# DAC_Production.net
KiCad netlist of a schematic drawn in EAGLE
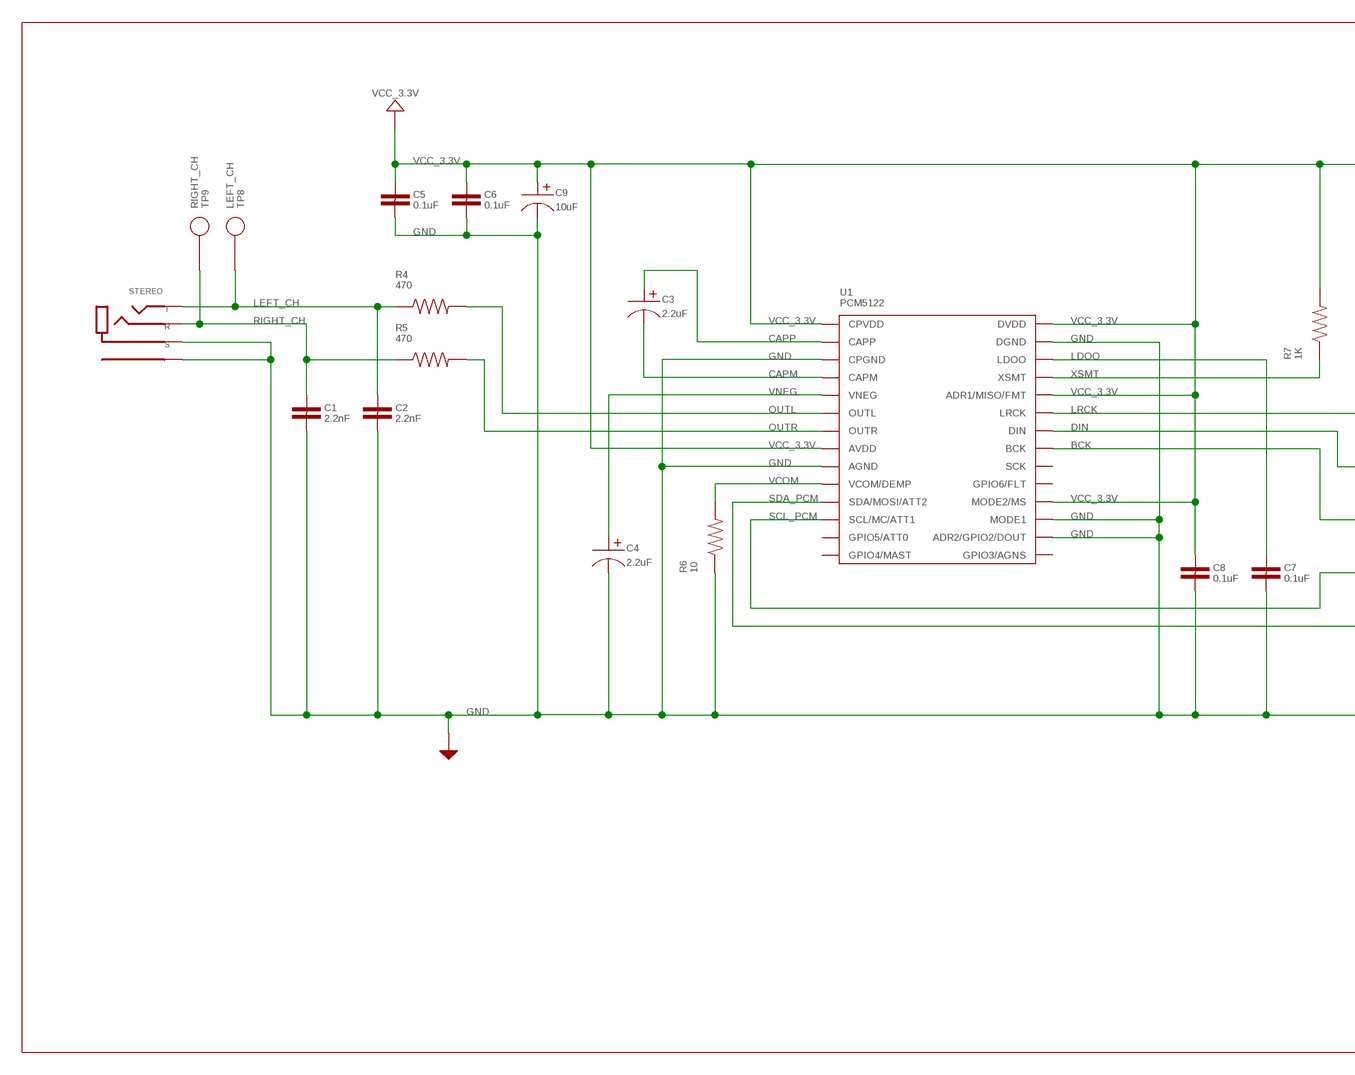
[diagram p0: schematic, sheet 1, part 1 of 2]
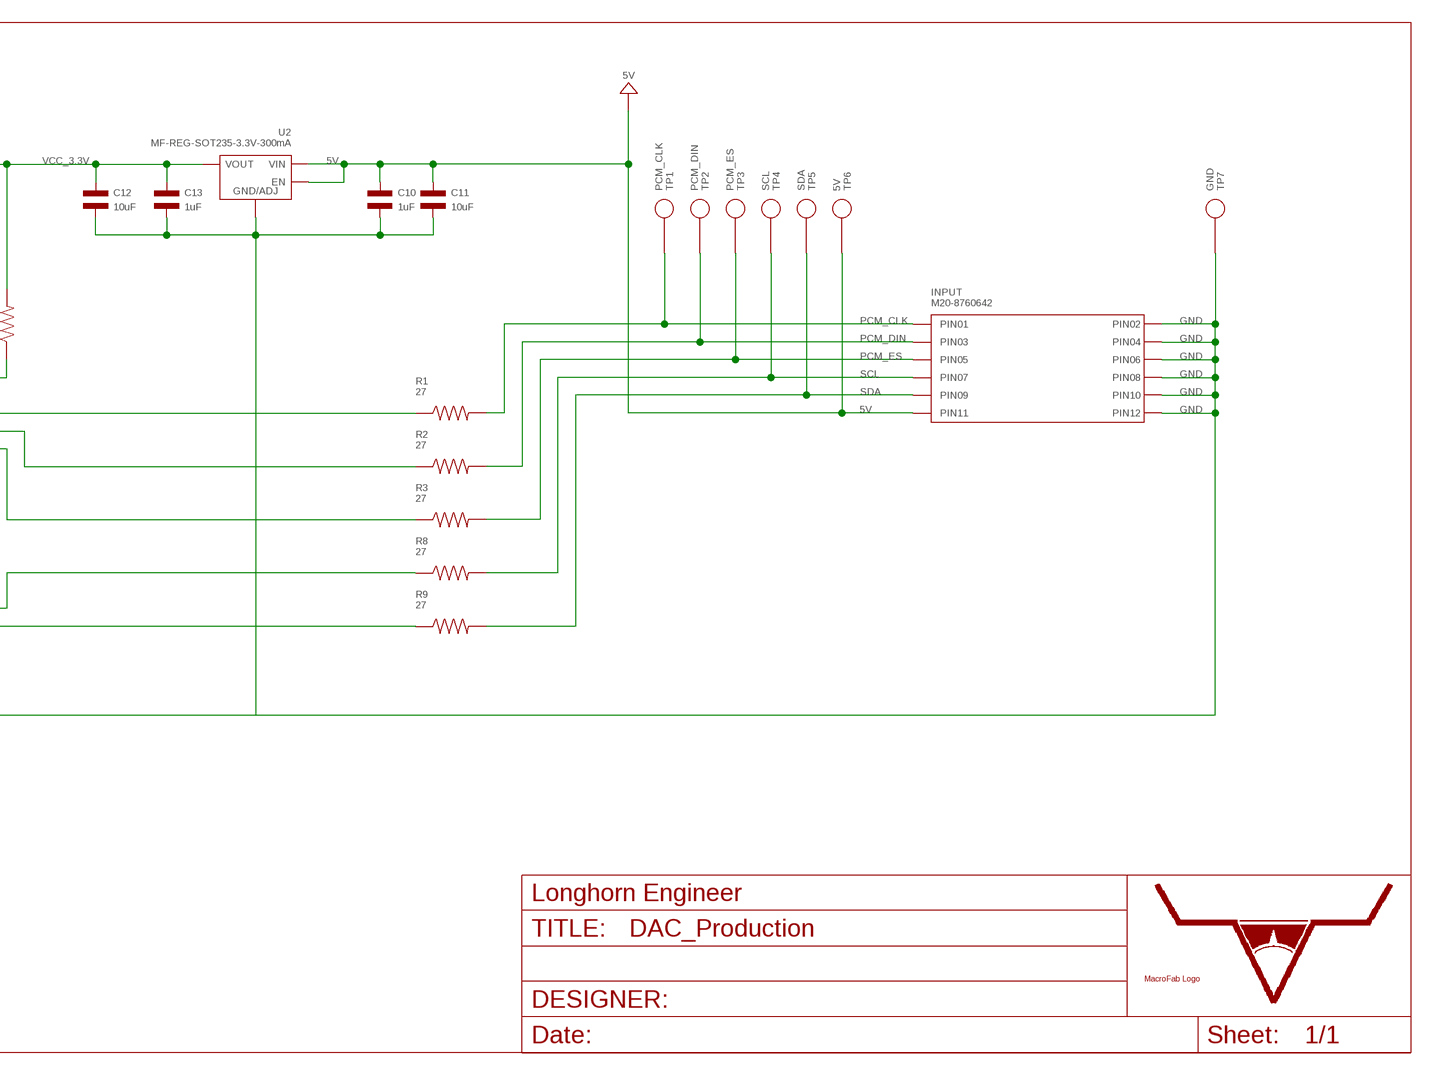
[diagram p1: schematic, sheet 1, part 2 of 2]

(export (version "E")
  (design (tool "Eeschema 10.0.6"))
  (components
    (comp (ref "C1")
      (value "2.2nF")
      (footprint "eagle-import:0805")
      (fields (field (name "MPN") "VJ0805A222KXXPW1BC"))
      (libsource (lib "eagle-import") (part "CAPACITOR_NON_POLAR_0805"))
    )
    (comp (ref "C2")
      (value "2.2nF")
      (footprint "eagle-import:0805")
      (fields (field (name "MPN") "VJ0805A222KXXPW1BC"))
      (libsource (lib "eagle-import") (part "CAPACITOR_NON_POLAR_0805"))
    )
    (comp (ref "C3")
      (value "2.2uF")
      (footprint "eagle-import:CP4MM")
      (fields (field (name "MPN") "UUQ1H2R2MCL1GB"))
      (libsource (lib "eagle-import") (part "CAPACITOR_P_4MM"))
    )
    (comp (ref "C4")
      (value "2.2uF")
      (footprint "eagle-import:CP4MM")
      (fields (field (name "MPN") "UUQ1H2R2MCL1GB"))
      (libsource (lib "eagle-import") (part "CAPACITOR_P_4MM"))
    )
    (comp (ref "C5")
      (value "0.1uF")
      (footprint "eagle-import:0805")
      (fields (field (name "MPN") "885012207072"))
      (libsource (lib "eagle-import") (part "CAPACITOR_NON_POLAR_0805"))
    )
    (comp (ref "C6")
      (value "0.1uF")
      (footprint "eagle-import:0805")
      (fields (field (name "MPN") "885012207072"))
      (libsource (lib "eagle-import") (part "CAPACITOR_NON_POLAR_0805"))
    )
    (comp (ref "C7")
      (value "0.1uF")
      (footprint "eagle-import:0805")
      (fields (field (name "MPN") "885012207072"))
      (libsource (lib "eagle-import") (part "CAPACITOR_NON_POLAR_0805"))
    )
    (comp (ref "C8")
      (value "0.1uF")
      (footprint "eagle-import:0805")
      (fields (field (name "MPN") "885012207072"))
      (libsource (lib "eagle-import") (part "CAPACITOR_NON_POLAR_0805"))
    )
    (comp (ref "C9")
      (value "10uF")
      (footprint "eagle-import:CP4MM")
      (fields (field (name "MPN") "UUQ1A100MCL1GB "))
      (libsource (lib "eagle-import") (part "CAPACITOR_P_4MM"))
    )
    (comp (ref "C10")
      (value "1uF")
      (footprint "eagle-import:C0805")
      (fields (field (name "MPN") "MF-CAP-0805-1uF"))
      (libsource (lib "eagle-import") (part "CAPACITOR_NP_0805"))
    )
    (comp (ref "C11")
      (value "10uF")
      (footprint "eagle-import:C1206")
      (fields (field (name "MPN") "MF-CAP-1206-10uF"))
      (libsource (lib "eagle-import") (part "CAPACITOR_NP_1206"))
    )
    (comp (ref "C12")
      (value "10uF")
      (footprint "eagle-import:C1206")
      (fields (field (name "MPN") "MF-CAP-1206-10uF"))
      (libsource (lib "eagle-import") (part "CAPACITOR_NP_1206"))
    )
    (comp (ref "C13")
      (value "1uF")
      (footprint "eagle-import:C0805")
      (fields (field (name "MPN") "MF-CAP-0805-1uF"))
      (libsource (lib "eagle-import") (part "CAPACITOR_NP_0805"))
    )
    (comp (ref "INPUT")
      (value "M20-8760642")
      (footprint "eagle-import:M20-8760642")
      (fields
        (field (name "LABEL01") "PCM_CLK")
        (field (name "LABEL02") "GND")
        (field (name "LABEL03") "PCM_DIN")
        (field (name "LABEL04") "GND")
        (field (name "LABEL05") "PCM_ES")
        (field (name "LABEL06") "GND")
        (field (name "LABEL07") "SCL")
        (field (name "LABEL08") "GND")
        (field (name "LABEL09") "SDA")
        (field (name "LABEL10") "GND")
        (field (name "LABEL11") "5V")
        (field (name "LABEL12") "GND")
      )
      (libsource (lib "eagle-import") (part "CON_02X06_M20-8760642"))
    )
    (comp (ref "R1")
      (value "27")
      (footprint "eagle-import:0603")
      (fields (field (name "MPN") "MF-RES-0603-27"))
      (libsource (lib "eagle-import") (part "RESISTOR_0603"))
    )
    (comp (ref "R2")
      (value "27")
      (footprint "eagle-import:0603")
      (fields (field (name "MPN") "MF-RES-0603-27"))
      (libsource (lib "eagle-import") (part "RESISTOR_0603"))
    )
    (comp (ref "R3")
      (value "27")
      (footprint "eagle-import:0603")
      (fields (field (name "MPN") "MF-RES-0603-27"))
      (libsource (lib "eagle-import") (part "RESISTOR_0603"))
    )
    (comp (ref "R4")
      (value "470")
      (footprint "eagle-import:0603")
      (fields (field (name "MPN") "MF-RES-0603-470"))
      (libsource (lib "eagle-import") (part "RESISTOR_0603"))
    )
    (comp (ref "R5")
      (value "470")
      (footprint "eagle-import:0603")
      (fields (field (name "MPN") "MF-RES-0603-470"))
      (libsource (lib "eagle-import") (part "RESISTOR_0603"))
    )
    (comp (ref "R6")
      (value "10")
      (footprint "eagle-import:0603")
      (fields (field (name "MPN") "MF-RES-0603-10"))
      (libsource (lib "eagle-import") (part "RESISTOR_0603"))
    )
    (comp (ref "R7")
      (value "1K")
      (footprint "eagle-import:0603")
      (fields (field (name "MPN") "MF-RES-0603-1K"))
      (libsource (lib "eagle-import") (part "RESISTOR_0603"))
    )
    (comp (ref "R8")
      (value "27")
      (footprint "eagle-import:0603")
      (fields (field (name "MPN") "MF-RES-0603-27"))
      (libsource (lib "eagle-import") (part "RESISTOR_0603"))
    )
    (comp (ref "R9")
      (value "27")
      (footprint "eagle-import:0603")
      (fields (field (name "MPN") "MF-RES-0603-27"))
      (libsource (lib "eagle-import") (part "RESISTOR_0603"))
    )
    (comp (ref "STEREO")
      (value "TRS_SHIELD_JACK_SJ1-3533NS")
      (footprint "eagle-import:SJ1-3533NS")
      (libsource (lib "eagle-import") (part "TRS_SHIELD_JACK_SJ1-3533NS"))
    )
    (comp (ref "TP1")
      (value "PCM_CLK")
      (footprint "eagle-import:ROUND_TP")
      (libsource (lib "eagle-import") (part "TEST_POINT_SINGLE_ROUND_1MM"))
    )
    (comp (ref "TP2")
      (value "PCM_DIN")
      (footprint "eagle-import:ROUND_TP")
      (libsource (lib "eagle-import") (part "TEST_POINT_SINGLE_ROUND_1MM"))
    )
    (comp (ref "TP3")
      (value "PCM_ES")
      (footprint "eagle-import:ROUND_TP")
      (libsource (lib "eagle-import") (part "TEST_POINT_SINGLE_ROUND_1MM"))
    )
    (comp (ref "TP4")
      (value "SCL")
      (footprint "eagle-import:ROUND_TP")
      (libsource (lib "eagle-import") (part "TEST_POINT_SINGLE_ROUND_1MM"))
    )
    (comp (ref "TP5")
      (value "SDA")
      (footprint "eagle-import:ROUND_TP")
      (libsource (lib "eagle-import") (part "TEST_POINT_SINGLE_ROUND_1MM"))
    )
    (comp (ref "TP6")
      (value "5V")
      (footprint "eagle-import:ROUND_TP")
      (libsource (lib "eagle-import") (part "TEST_POINT_SINGLE_ROUND_1MM"))
    )
    (comp (ref "TP7")
      (value "GND")
      (footprint "eagle-import:ROUND_TP")
      (libsource (lib "eagle-import") (part "TEST_POINT_SINGLE_ROUND_1MM"))
    )
    (comp (ref "TP8")
      (value "LEFT_CH")
      (footprint "eagle-import:ROUND_TP")
      (libsource (lib "eagle-import") (part "TEST_POINT_SINGLE_ROUND_1MM"))
    )
    (comp (ref "TP9")
      (value "RIGHT_CH")
      (footprint "eagle-import:ROUND_TP")
      (libsource (lib "eagle-import") (part "TEST_POINT_SINGLE_ROUND_1MM"))
    )
    (comp (ref "U$8")
      (value "LHE_FRAME")
      (footprint "eagle-import:LHE_FRAME")
      (fields (field (name "DNAME") "Parker Dillmann") (field (name "REVNUM") "REV 2"))
      (libsource (lib "eagle-import") (part "LHE_FRAME"))
    )
    (comp (ref "U$9")
      (value "MF_LOGOLOGO_MEDIUM")
      (footprint "eagle-import:MF_LOGO_MEDIUM")
      (libsource (lib "eagle-import") (part "MF_LOGOLOGO_MEDIUM"))
    )
    (comp (ref "U1")
      (value "PCM5122")
      (footprint "eagle-import:PCM5122_TTSOP-28")
      (libsource (lib "eagle-import") (part "PCM512X"))
    )
    (comp (ref "U2")
      (value "MF-REG-SOT235-3.3V-300mA")
      (footprint "eagle-import:SOT-23-5")
      (fields (field (name "HOUSEPART") "YES"))
      (libsource (lib "eagle-import") (part "TLV70233PDBVR"))
    )
  )
  (nets
    (net (code "1") (name "/BCK") (class "Default")
      (node (ref "R3") (pin "1") (pinfunction "1_1") (pintype "passive"))
      (node (ref "U1") (pin "P$21") (pinfunction "BCK_P$21") (pintype "bidirectional"))
    )
    (net (code "2") (name "/CAPM") (class "Default")
      (node (ref "C3") (pin "P$2") (pinfunction "P$2_P$2") (pintype "passive"))
      (node (ref "U1") (pin "P$4") (pinfunction "CAPM_P$4") (pintype "bidirectional"))
    )
    (net (code "3") (name "/CAPP") (class "Default")
      (node (ref "C3") (pin "P$1") (pinfunction "P$1_P$1") (pintype "passive"))
      (node (ref "U1") (pin "P$2") (pinfunction "CAPP_P$2") (pintype "bidirectional"))
    )
    (net (code "4") (name "/DIN") (class "Default")
      (node (ref "R2") (pin "1") (pinfunction "1_1") (pintype "passive"))
      (node (ref "U1") (pin "P$22") (pinfunction "DIN_P$22") (pintype "bidirectional"))
    )
    (net (code "5") (name "/LDOO") (class "Default")
      (node (ref "C7") (pin "1") (pinfunction "1_1") (pintype "passive"))
      (node (ref "U1") (pin "P$26") (pinfunction "LDOO_P$26") (pintype "bidirectional"))
    )
    (net (code "6") (name "/LEFT_CH") (class "Default")
      (node (ref "C2") (pin "1") (pinfunction "1_1") (pintype "passive"))
      (node (ref "R4") (pin "1") (pinfunction "1_1") (pintype "passive"))
      (node (ref "STEREO") (pin "2_A") (pinfunction "T_2_A") (pintype "bidirectional"))
      (node (ref "STEREO") (pin "2_B") (pinfunction "T_2_B") (pintype "bidirectional"))
      (node (ref "TP8") (pin "P$1") (pinfunction "P$1_P$1") (pintype "bidirectional"))
    )
    (net (code "7") (name "/LRCK") (class "Default")
      (node (ref "R1") (pin "1") (pinfunction "1_1") (pintype "passive"))
      (node (ref "U1") (pin "P$23") (pinfunction "LRCK_P$23") (pintype "bidirectional"))
    )
    (net (code "8") (name "/OUTL") (class "Default")
      (node (ref "R4") (pin "2") (pinfunction "2_2") (pintype "passive"))
      (node (ref "U1") (pin "P$6") (pinfunction "OUTL_P$6") (pintype "bidirectional"))
    )
    (net (code "9") (name "/OUTR") (class "Default")
      (node (ref "R5") (pin "2") (pinfunction "2_2") (pintype "passive"))
      (node (ref "U1") (pin "P$7") (pinfunction "OUTR_P$7") (pintype "bidirectional"))
    )
    (net (code "10") (name "/PCM_CLK") (class "Default")
      (node (ref "INPUT") (pin "P$1") (pinfunction "PIN1_P$1") (pintype "bidirectional"))
      (node (ref "R1") (pin "2") (pinfunction "2_2") (pintype "passive"))
      (node (ref "TP1") (pin "P$1") (pinfunction "P$1_P$1") (pintype "bidirectional"))
    )
    (net (code "11") (name "/PCM_DIN") (class "Default")
      (node (ref "INPUT") (pin "P$3") (pinfunction "PIN3_P$3") (pintype "bidirectional"))
      (node (ref "R2") (pin "2") (pinfunction "2_2") (pintype "passive"))
      (node (ref "TP2") (pin "P$1") (pinfunction "P$1_P$1") (pintype "bidirectional"))
    )
    (net (code "12") (name "/PCM_ES") (class "Default")
      (node (ref "INPUT") (pin "P$5") (pinfunction "PIN5_P$5") (pintype "bidirectional"))
      (node (ref "R3") (pin "2") (pinfunction "2_2") (pintype "passive"))
      (node (ref "TP3") (pin "P$1") (pinfunction "P$1_P$1") (pintype "bidirectional"))
    )
    (net (code "13") (name "/RIGHT_CH") (class "Default")
      (node (ref "C1") (pin "1") (pinfunction "1_1") (pintype "passive"))
      (node (ref "R5") (pin "1") (pinfunction "1_1") (pintype "passive"))
      (node (ref "STEREO") (pin "3_A") (pinfunction "R_3_A") (pintype "bidirectional"))
      (node (ref "STEREO") (pin "3_B") (pinfunction "R_3_B") (pintype "bidirectional"))
      (node (ref "TP9") (pin "P$1") (pinfunction "P$1_P$1") (pintype "bidirectional"))
    )
    (net (code "14") (name "/SCL") (class "Default")
      (node (ref "INPUT") (pin "P$7") (pinfunction "PIN7_P$7") (pintype "bidirectional"))
      (node (ref "R8") (pin "2") (pinfunction "2_2") (pintype "passive"))
      (node (ref "TP4") (pin "P$1") (pinfunction "P$1_P$1") (pintype "bidirectional"))
    )
    (net (code "15") (name "/SCL_PCM") (class "Default")
      (node (ref "R8") (pin "1") (pinfunction "1_1") (pintype "passive"))
      (node (ref "U1") (pin "P$12") (pinfunction "SCL/MC/ATT1_P$12") (pintype "bidirectional"))
    )
    (net (code "16") (name "/SDA") (class "Default")
      (node (ref "INPUT") (pin "P$9") (pinfunction "PIN9_P$9") (pintype "bidirectional"))
      (node (ref "R9") (pin "2") (pinfunction "2_2") (pintype "passive"))
      (node (ref "TP5") (pin "P$1") (pinfunction "P$1_P$1") (pintype "bidirectional"))
    )
    (net (code "17") (name "/SDA_PCM") (class "Default")
      (node (ref "R9") (pin "1") (pinfunction "1_1") (pintype "passive"))
      (node (ref "U1") (pin "P$11") (pinfunction "SDA/MOSI/ATT2_P$11") (pintype "bidirectional"))
    )
    (net (code "18") (name "/VCOM") (class "Default")
      (node (ref "R6") (pin "2") (pinfunction "2_2") (pintype "passive"))
      (node (ref "U1") (pin "P$10") (pinfunction "VCOM/DEMP_P$10") (pintype "bidirectional"))
    )
    (net (code "19") (name "/VNEG") (class "Default")
      (node (ref "C4") (pin "P$1") (pinfunction "P$1_P$1") (pintype "passive"))
      (node (ref "U1") (pin "P$5") (pinfunction "VNEG_P$5") (pintype "bidirectional"))
    )
    (net (code "20") (name "/XSMT") (class "Default")
      (node (ref "R7") (pin "1") (pinfunction "1_1") (pintype "passive"))
      (node (ref "U1") (pin "P$25") (pinfunction "XSMT_P$25") (pintype "bidirectional"))
    )
    (net (code "21") (name "5V") (class "Default")
      (node (ref "C10") (pin "P$1") (pinfunction "P$1_P$1") (pintype "passive"))
      (node (ref "C11") (pin "P$1") (pinfunction "P$1_P$1") (pintype "passive"))
      (node (ref "INPUT") (pin "P$11") (pinfunction "PIN11_P$11") (pintype "bidirectional"))
      (node (ref "TP6") (pin "P$1") (pinfunction "P$1_P$1") (pintype "bidirectional"))
      (node (ref "U2") (pin "P$1") (pinfunction "VIN_P$1") (pintype "bidirectional"))
      (node (ref "U2") (pin "P$3") (pinfunction "EN_P$3") (pintype "bidirectional"))
    )
    (net (code "22") (name "GND_RAIL") (class "Default")
      (node (ref "C1") (pin "2") (pinfunction "2_2") (pintype "passive"))
      (node (ref "C10") (pin "P$2") (pinfunction "P$2_P$2") (pintype "passive"))
      (node (ref "C11") (pin "P$2") (pinfunction "P$2_P$2") (pintype "passive"))
      (node (ref "C12") (pin "P$2") (pinfunction "P$2_P$2") (pintype "passive"))
      (node (ref "C13") (pin "P$2") (pinfunction "P$2_P$2") (pintype "passive"))
      (node (ref "C2") (pin "2") (pinfunction "2_2") (pintype "passive"))
      (node (ref "C4") (pin "P$2") (pinfunction "P$2_P$2") (pintype "passive"))
      (node (ref "C5") (pin "2") (pinfunction "2_2") (pintype "passive"))
      (node (ref "C6") (pin "2") (pinfunction "2_2") (pintype "passive"))
      (node (ref "C7") (pin "2") (pinfunction "2_2") (pintype "passive"))
      (node (ref "C8") (pin "2") (pinfunction "2_2") (pintype "passive"))
      (node (ref "C9") (pin "P$2") (pinfunction "P$2_P$2") (pintype "passive"))
      (node (ref "INPUT") (pin "P$10") (pinfunction "PIN10_P$10") (pintype "bidirectional"))
      (node (ref "INPUT") (pin "P$12") (pinfunction "PIN12_P$12") (pintype "bidirectional"))
      (node (ref "INPUT") (pin "P$2") (pinfunction "PIN2_P$2") (pintype "bidirectional"))
      (node (ref "INPUT") (pin "P$4") (pinfunction "PIN4_P$4") (pintype "bidirectional"))
      (node (ref "INPUT") (pin "P$6") (pinfunction "PIN6_P$6") (pintype "bidirectional"))
      (node (ref "INPUT") (pin "P$8") (pinfunction "PIN8_P$8") (pintype "bidirectional"))
      (node (ref "R6") (pin "1") (pinfunction "1_1") (pintype "passive"))
      (node (ref "STEREO") (pin "1_A") (pinfunction "S_1_A") (pintype "bidirectional"))
      (node (ref "STEREO") (pin "1_B") (pinfunction "S_1_B") (pintype "bidirectional"))
      (node (ref "STEREO") (pin "S1") (pinfunction "SHIELD_S1") (pintype "bidirectional"))
      (node (ref "STEREO") (pin "S2") (pinfunction "SHIELD_S2") (pintype "bidirectional"))
      (node (ref "STEREO") (pin "S3") (pinfunction "SHIELD_S3") (pintype "bidirectional"))
      (node (ref "STEREO") (pin "S4") (pinfunction "SHIELD_S4") (pintype "bidirectional"))
      (node (ref "STEREO") (pin "S5") (pinfunction "SHIELD_S5") (pintype "bidirectional"))
      (node (ref "STEREO") (pin "S6") (pinfunction "SHIELD_S6") (pintype "bidirectional"))
      (node (ref "TP7") (pin "P$1") (pinfunction "P$1_P$1") (pintype "bidirectional"))
      (node (ref "U1") (pin "P$16") (pinfunction "ADR2/GPIO2/DOUT_P$16") (pintype "bidirectional"))
      (node (ref "U1") (pin "P$17") (pinfunction "MODE1_P$17") (pintype "bidirectional"))
      (node (ref "U1") (pin "P$27") (pinfunction "DGND_P$27") (pintype "bidirectional"))
      (node (ref "U1") (pin "P$3") (pinfunction "CPGND_P$3") (pintype "bidirectional"))
      (node (ref "U1") (pin "P$9") (pinfunction "AGND_P$9") (pintype "bidirectional"))
      (node (ref "U2") (pin "P$2") (pinfunction "GND/ADJ_P$2") (pintype "bidirectional"))
    )
    (net (code "23") (name "VCC_3.3V") (class "Default")
      (node (ref "C12") (pin "P$1") (pinfunction "P$1_P$1") (pintype "passive"))
      (node (ref "C13") (pin "P$1") (pinfunction "P$1_P$1") (pintype "passive"))
      (node (ref "C5") (pin "1") (pinfunction "1_1") (pintype "passive"))
      (node (ref "C6") (pin "1") (pinfunction "1_1") (pintype "passive"))
      (node (ref "C8") (pin "1") (pinfunction "1_1") (pintype "passive"))
      (node (ref "C9") (pin "P$1") (pinfunction "P$1_P$1") (pintype "passive"))
      (node (ref "R7") (pin "2") (pinfunction "2_2") (pintype "passive"))
      (node (ref "U1") (pin "P$1") (pinfunction "CPVDD_P$1") (pintype "bidirectional"))
      (node (ref "U1") (pin "P$18") (pinfunction "MODE2/MS_P$18") (pintype "bidirectional"))
      (node (ref "U1") (pin "P$24") (pinfunction "ADR1/MISO/FMT_P$24") (pintype "bidirectional"))
      (node (ref "U1") (pin "P$28") (pinfunction "DVDD_P$28") (pintype "bidirectional"))
      (node (ref "U1") (pin "P$8") (pinfunction "AVDD_P$8") (pintype "bidirectional"))
      (node (ref "U2") (pin "P$5") (pinfunction "VOUT_P$5") (pintype "bidirectional"))
    )
    (net (code "24") (name "unconnected-(U1-GPIO3{slash}AGNS-PadP$15)") (class "Default")
      (node (ref "U1") (pin "P$15") (pinfunction "GPIO3/AGNS_P$15") (pintype "bidirectional"))
    )
    (net (code "25") (name "unconnected-(U1-GPIO4{slash}MAST-PadP$14)") (class "Default")
      (node (ref "U1") (pin "P$14") (pinfunction "GPIO4/MAST_P$14") (pintype "bidirectional"))
    )
    (net (code "26") (name "unconnected-(U1-GPIO5{slash}ATT0-PadP$13)") (class "Default")
      (node (ref "U1") (pin "P$13") (pinfunction "GPIO5/ATT0_P$13") (pintype "bidirectional"))
    )
    (net (code "27") (name "unconnected-(U1-GPIO6{slash}FLT-PadP$19)") (class "Default")
      (node (ref "U1") (pin "P$19") (pinfunction "GPIO6/FLT_P$19") (pintype "bidirectional"))
    )
    (net (code "28") (name "unconnected-(U1-SCK-PadP$20)") (class "Default")
      (node (ref "U1") (pin "P$20") (pinfunction "SCK_P$20") (pintype "bidirectional"))
    )
  )
)
